# ILX_Sheet.net
KiCad netlist of a schematic drawn in Altium Designer
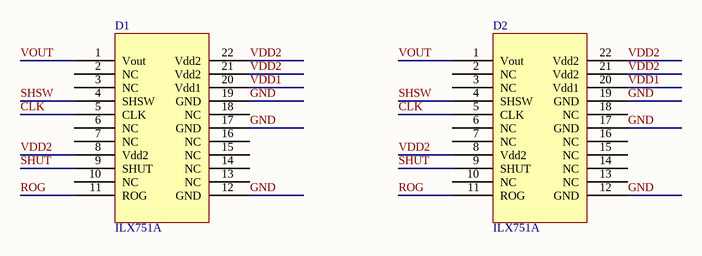
[diagram p0: ILX_Sheet.SchDoc]

(export (version "E")
  (design (tool "Eeschema 10.0.6"))
  (components
    (comp (ref "D1") (value "ILX751A") (footprint "ILX751A") (libsource (lib "MIT_Schlib") (part "ILX751A")))
    (comp (ref "D2")
      (value "ILX751A")
      (footprint "ILX751A - Module")
      (libsource (lib "MIT_Schlib") (part "ILX751A_module"))
    )
  )
  (nets
    (net (code "1") (name "/CLK") (class "Default")
      (node (ref "D1") (pin "5") (pinfunction "CLK_5") (pintype "passive"))
      (node (ref "D2") (pin "5") (pinfunction "CLK_5") (pintype "passive"))
    )
    (net (code "2") (name "/GND") (class "Default")
      (node (ref "D1") (pin "12") (pinfunction "GND_12") (pintype "passive"))
      (node (ref "D1") (pin "17") (pinfunction "GND_17") (pintype "passive"))
      (node (ref "D1") (pin "19") (pinfunction "GND_19") (pintype "passive"))
      (node (ref "D2") (pin "12") (pinfunction "GND_12") (pintype "passive"))
      (node (ref "D2") (pin "17") (pinfunction "GND_17") (pintype "passive"))
      (node (ref "D2") (pin "19") (pinfunction "GND_19") (pintype "passive"))
    )
    (net (code "3") (name "/ROG") (class "Default")
      (node (ref "D1") (pin "11") (pinfunction "ROG_11") (pintype "passive"))
      (node (ref "D2") (pin "11") (pinfunction "ROG_11") (pintype "passive"))
    )
    (net (code "4") (name "/SHSW") (class "Default")
      (node (ref "D1") (pin "4") (pinfunction "SHSW_4") (pintype "passive"))
      (node (ref "D2") (pin "4") (pinfunction "SHSW_4") (pintype "passive"))
    )
    (net (code "5") (name "/SHUT") (class "Default")
      (node (ref "D1") (pin "9") (pinfunction "SHUT_9") (pintype "passive"))
      (node (ref "D2") (pin "9") (pinfunction "SHUT_9") (pintype "passive"))
    )
    (net (code "6") (name "/VDD1") (class "Default")
      (node (ref "D1") (pin "20") (pinfunction "Vdd1_20") (pintype "passive"))
      (node (ref "D2") (pin "20") (pinfunction "Vdd1_20") (pintype "passive"))
    )
    (net (code "7") (name "/VDD2") (class "Default")
      (node (ref "D1") (pin "21") (pinfunction "Vdd2_21") (pintype "passive"))
      (node (ref "D1") (pin "22") (pinfunction "Vdd2_22") (pintype "passive"))
      (node (ref "D1") (pin "8") (pinfunction "Vdd2_8") (pintype "passive"))
      (node (ref "D2") (pin "21") (pinfunction "Vdd2_21") (pintype "passive"))
      (node (ref "D2") (pin "22") (pinfunction "Vdd2_22") (pintype "passive"))
      (node (ref "D2") (pin "8") (pinfunction "Vdd2_8") (pintype "passive"))
    )
    (net (code "8") (name "/VOUT") (class "Default")
      (node (ref "D1") (pin "1") (pinfunction "Vout_1") (pintype "passive"))
      (node (ref "D2") (pin "1") (pinfunction "Vout_1") (pintype "passive"))
    )
    (net (code "9") (name "unconnected-(D1-NC-Pad2)") (class "Default")
      (node (ref "D1") (pin "2") (pinfunction "NC_2") (pintype "passive"))
    )
    (net (code "10") (name "unconnected-(D1-NC-Pad3)") (class "Default")
      (node (ref "D1") (pin "3") (pinfunction "NC_3") (pintype "passive"))
    )
    (net (code "11") (name "unconnected-(D1-NC-Pad6)") (class "Default")
      (node (ref "D1") (pin "6") (pinfunction "NC_6") (pintype "passive"))
    )
    (net (code "12") (name "unconnected-(D1-NC-Pad7)") (class "Default")
      (node (ref "D1") (pin "7") (pinfunction "NC_7") (pintype "passive"))
    )
    (net (code "13") (name "unconnected-(D1-NC-Pad10)") (class "Default")
      (node (ref "D1") (pin "10") (pinfunction "NC_10") (pintype "passive"))
    )
    (net (code "14") (name "unconnected-(D1-NC-Pad13)") (class "Default")
      (node (ref "D1") (pin "13") (pinfunction "NC_13") (pintype "passive"))
    )
    (net (code "15") (name "unconnected-(D1-NC-Pad14)") (class "Default")
      (node (ref "D1") (pin "14") (pinfunction "NC_14") (pintype "passive"))
    )
    (net (code "16") (name "unconnected-(D1-NC-Pad15)") (class "Default")
      (node (ref "D1") (pin "15") (pinfunction "NC_15") (pintype "passive"))
    )
    (net (code "17") (name "unconnected-(D1-NC-Pad16)") (class "Default")
      (node (ref "D1") (pin "16") (pinfunction "NC_16") (pintype "passive"))
    )
    (net (code "18") (name "unconnected-(D1-NC-Pad18)") (class "Default")
      (node (ref "D1") (pin "18") (pinfunction "NC_18") (pintype "passive"))
    )
    (net (code "19") (name "unconnected-(D2-NC-Pad2)") (class "Default")
      (node (ref "D2") (pin "2") (pinfunction "NC_2") (pintype "passive"))
    )
    (net (code "20") (name "unconnected-(D2-NC-Pad3)") (class "Default")
      (node (ref "D2") (pin "3") (pinfunction "NC_3") (pintype "passive"))
    )
    (net (code "21") (name "unconnected-(D2-NC-Pad6)") (class "Default")
      (node (ref "D2") (pin "6") (pinfunction "NC_6") (pintype "passive"))
    )
    (net (code "22") (name "unconnected-(D2-NC-Pad7)") (class "Default")
      (node (ref "D2") (pin "7") (pinfunction "NC_7") (pintype "passive"))
    )
    (net (code "23") (name "unconnected-(D2-NC-Pad10)") (class "Default")
      (node (ref "D2") (pin "10") (pinfunction "NC_10") (pintype "passive"))
    )
    (net (code "24") (name "unconnected-(D2-NC-Pad13)") (class "Default")
      (node (ref "D2") (pin "13") (pinfunction "NC_13") (pintype "passive"))
    )
    (net (code "25") (name "unconnected-(D2-NC-Pad14)") (class "Default")
      (node (ref "D2") (pin "14") (pinfunction "NC_14") (pintype "passive"))
    )
    (net (code "26") (name "unconnected-(D2-NC-Pad15)") (class "Default")
      (node (ref "D2") (pin "15") (pinfunction "NC_15") (pintype "passive"))
    )
    (net (code "27") (name "unconnected-(D2-NC-Pad16)") (class "Default")
      (node (ref "D2") (pin "16") (pinfunction "NC_16") (pintype "passive"))
    )
    (net (code "28") (name "unconnected-(D2-NC-Pad18)") (class "Default")
      (node (ref "D2") (pin "18") (pinfunction "NC_18") (pintype "passive"))
    )
  )
)
